# SNAC_USB3-mini.net
KiCad netlist of a schematic drawn in EAGLE
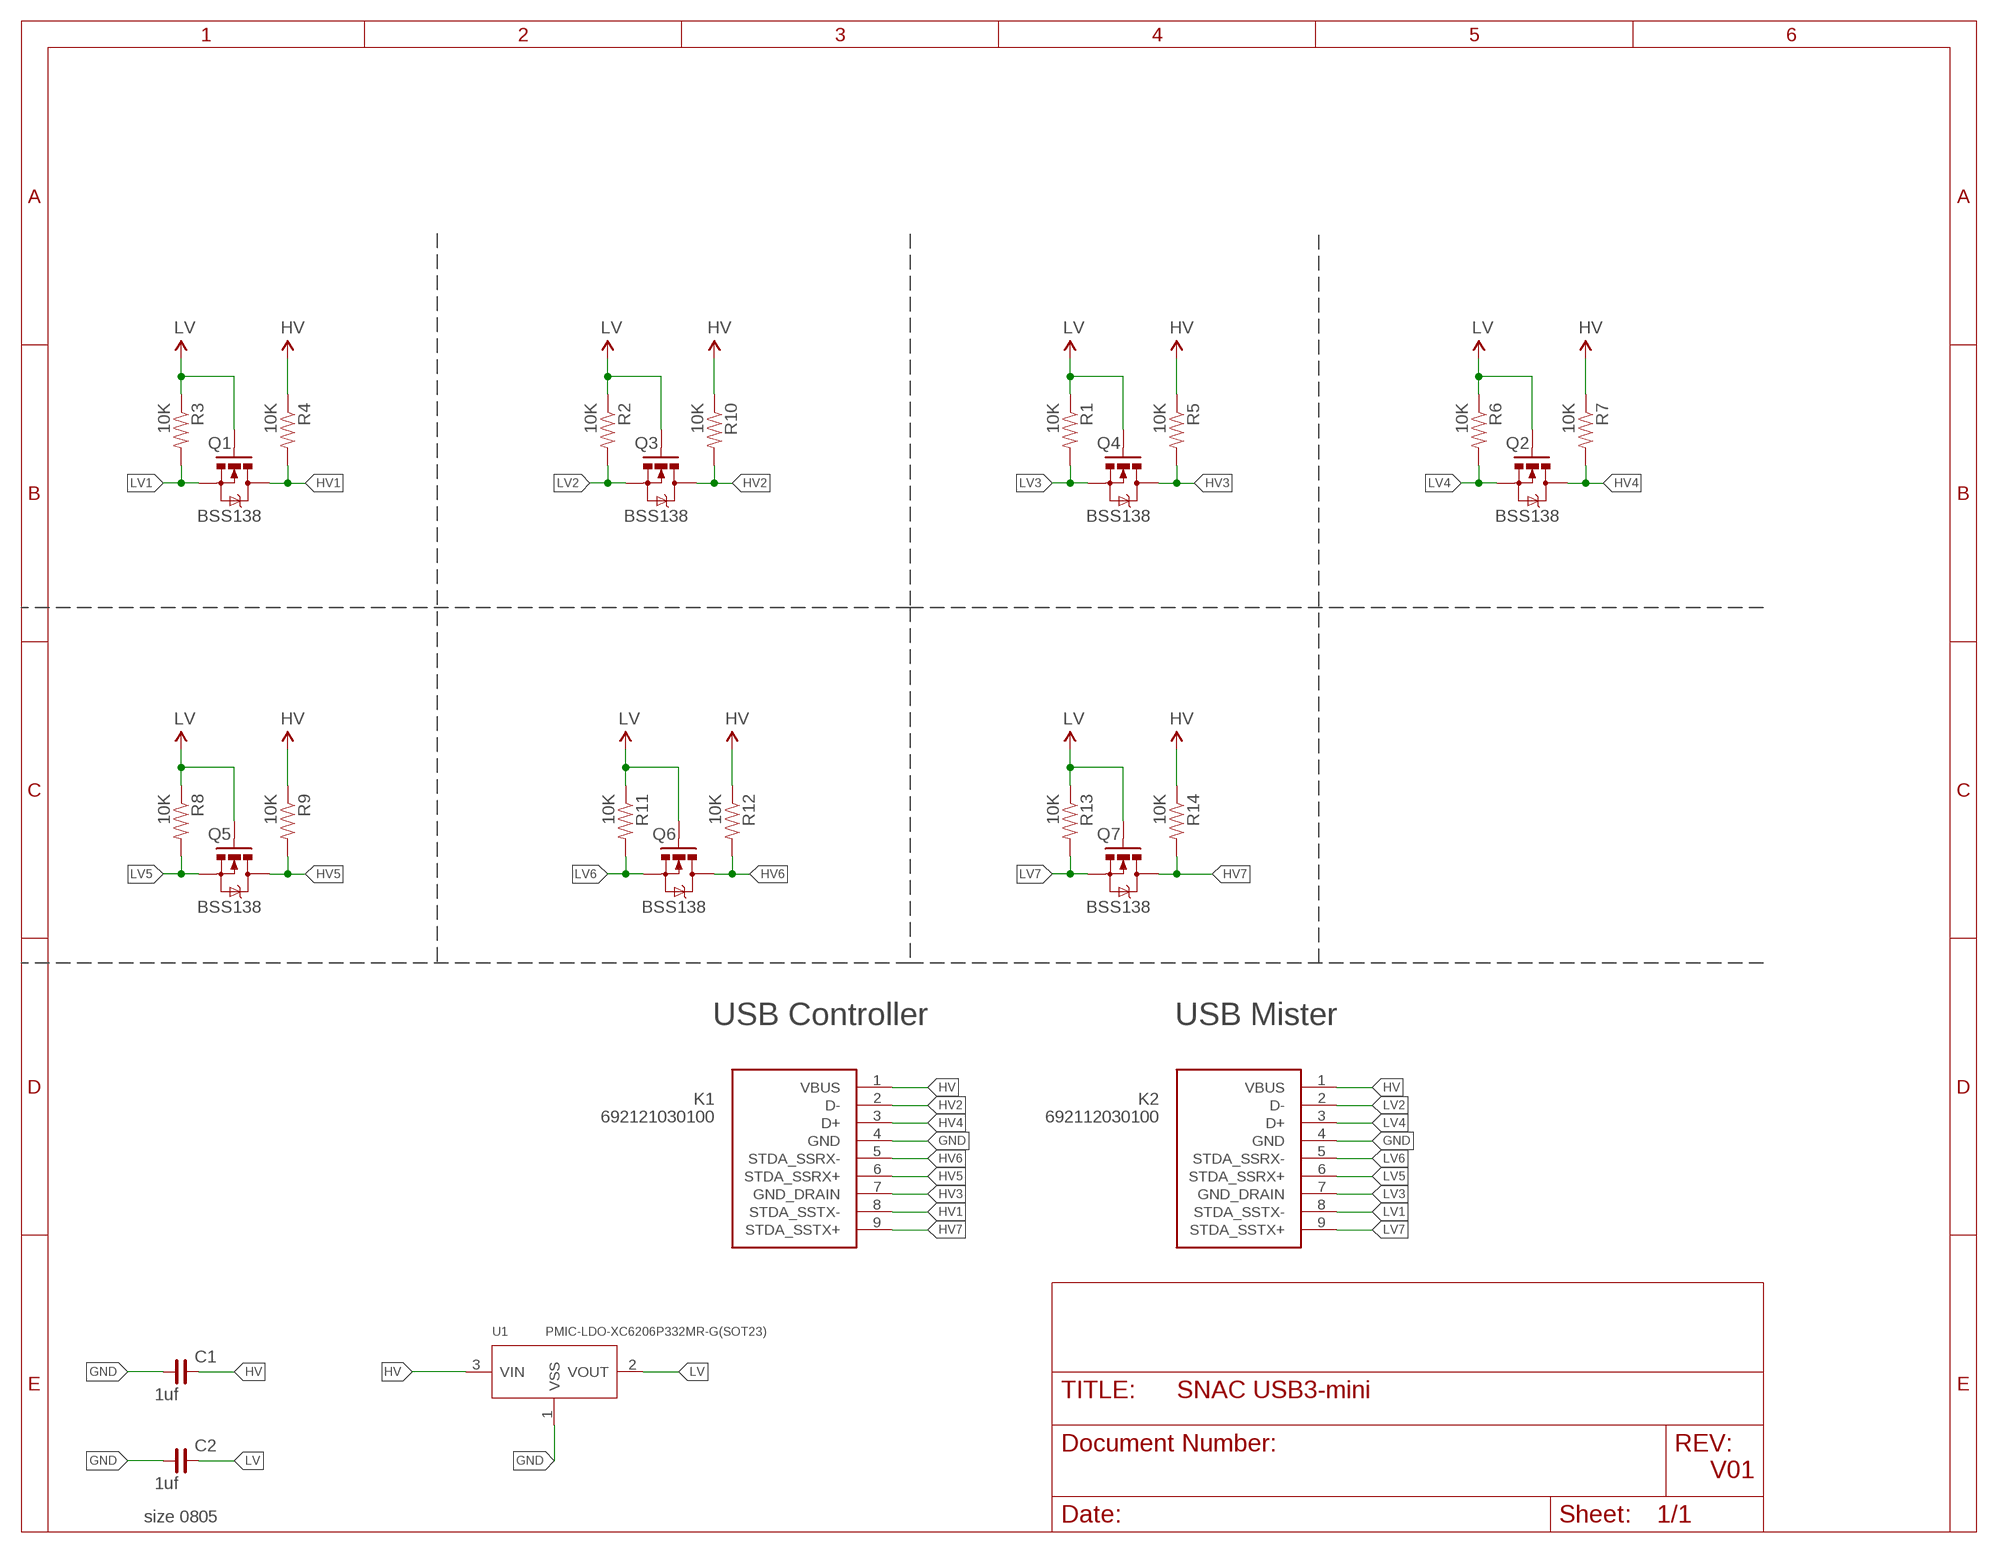
[diagram p0: schematic, sheet 1]

(export (version "E")
  (design (tool "Eeschema 10.0.6"))
  (components
    (comp (ref "C1")
      (value "1uf")
      (footprint "eagle-import:C0805")
      (libsource (lib "eagle-import") (part "C_0805"))
    )
    (comp (ref "C2")
      (value "1uf")
      (footprint "eagle-import:C0805")
      (libsource (lib "eagle-import") (part "C_0805"))
    )
    (comp (ref "K1")
      (value "692121030100")
      (footprint "eagle-import:692121030100")
      (libsource (lib "eagle-import") (part "692121030100"))
    )
    (comp (ref "K2")
      (value "692112030100")
      (footprint "eagle-import:692112030100")
      (libsource (lib "eagle-import") (part "692112030100"))
    )
    (comp (ref "Q1")
      (value "BSS138")
      (footprint "eagle-import:SOT23-3")
      (libsource (lib "eagle-import") (part "MOSFET-NCHANNELSMD"))
    )
    (comp (ref "Q2")
      (value "BSS138")
      (footprint "eagle-import:SOT23-3")
      (libsource (lib "eagle-import") (part "MOSFET-NCHANNELSMD"))
    )
    (comp (ref "Q3")
      (value "BSS138")
      (footprint "eagle-import:SOT23-3")
      (libsource (lib "eagle-import") (part "MOSFET-NCHANNELSMD"))
    )
    (comp (ref "Q4")
      (value "BSS138")
      (footprint "eagle-import:SOT23-3")
      (libsource (lib "eagle-import") (part "MOSFET-NCHANNELSMD"))
    )
    (comp (ref "Q5")
      (value "BSS138")
      (footprint "eagle-import:SOT23-3")
      (libsource (lib "eagle-import") (part "MOSFET-NCHANNELSMD"))
    )
    (comp (ref "Q6")
      (value "BSS138")
      (footprint "eagle-import:SOT23-3")
      (libsource (lib "eagle-import") (part "MOSFET-NCHANNELSMD"))
    )
    (comp (ref "Q7")
      (value "BSS138")
      (footprint "eagle-import:SOT23-3")
      (libsource (lib "eagle-import") (part "MOSFET-NCHANNELSMD"))
    )
    (comp (ref "R1")
      (value "10K")
      (footprint "eagle-import:0603-RES")
      (libsource (lib "eagle-import") (part "RESISTOR0603-RES"))
    )
    (comp (ref "R2")
      (value "10K")
      (footprint "eagle-import:0603-RES")
      (libsource (lib "eagle-import") (part "RESISTOR0603-RES"))
    )
    (comp (ref "R3")
      (value "10K")
      (footprint "eagle-import:0603-RES")
      (libsource (lib "eagle-import") (part "RESISTOR0603-RES"))
    )
    (comp (ref "R4")
      (value "10K")
      (footprint "eagle-import:0603-RES")
      (libsource (lib "eagle-import") (part "RESISTOR0603-RES"))
    )
    (comp (ref "R5")
      (value "10K")
      (footprint "eagle-import:0603-RES")
      (libsource (lib "eagle-import") (part "RESISTOR0603-RES"))
    )
    (comp (ref "R6")
      (value "10K")
      (footprint "eagle-import:0603-RES")
      (libsource (lib "eagle-import") (part "RESISTOR0603-RES"))
    )
    (comp (ref "R7")
      (value "10K")
      (footprint "eagle-import:0603-RES")
      (libsource (lib "eagle-import") (part "RESISTOR0603-RES"))
    )
    (comp (ref "R8")
      (value "10K")
      (footprint "eagle-import:0603-RES")
      (libsource (lib "eagle-import") (part "RESISTOR0603-RES"))
    )
    (comp (ref "R9")
      (value "10K")
      (footprint "eagle-import:0603-RES")
      (libsource (lib "eagle-import") (part "RESISTOR0603-RES"))
    )
    (comp (ref "R10")
      (value "10K")
      (footprint "eagle-import:0603-RES")
      (libsource (lib "eagle-import") (part "RESISTOR0603-RES"))
    )
    (comp (ref "R11")
      (value "10K")
      (footprint "eagle-import:0603-RES")
      (libsource (lib "eagle-import") (part "RESISTOR0603-RES"))
    )
    (comp (ref "R12")
      (value "10K")
      (footprint "eagle-import:0603-RES")
      (libsource (lib "eagle-import") (part "RESISTOR0603-RES"))
    )
    (comp (ref "R13")
      (value "10K")
      (footprint "eagle-import:0603-RES")
      (libsource (lib "eagle-import") (part "RESISTOR0603-RES"))
    )
    (comp (ref "R14")
      (value "10K")
      (footprint "eagle-import:0603-RES")
      (libsource (lib "eagle-import") (part "RESISTOR0603-RES"))
    )
    (comp (ref "U1")
      (value "PMIC-LDO-XC6206P332MR-G(SOT23)")
      (footprint "eagle-import:SOT-23")
      (fields (field (name "MF") "Torex") (field (name "MP") "XC6206P332MR-G"))
      (libsource (lib "eagle-import") (part "PMIC-LDO-XC6206P332MR-G(SOT23)"))
    )
  )
  (nets
    (net (code "1") (name "GND") (class "Default")
      (node (ref "C1") (pin "1") (pinfunction "1_1") (pintype "passive"))
      (node (ref "C2") (pin "1") (pinfunction "1_1") (pintype "passive"))
      (node (ref "K1") (pin "4") (pinfunction "GND_4") (pintype "bidirectional"))
      (node (ref "K2") (pin "4") (pinfunction "GND_4") (pintype "bidirectional"))
      (node (ref "U1") (pin "1") (pinfunction "VSS_1") (pintype "power_in"))
    )
    (net (code "2") (name "HV") (class "Default")
      (node (ref "C1") (pin "2") (pinfunction "2_2") (pintype "passive"))
      (node (ref "K1") (pin "1") (pinfunction "VBUS_1") (pintype "bidirectional"))
      (node (ref "K2") (pin "1") (pinfunction "VBUS_1") (pintype "bidirectional"))
      (node (ref "R10") (pin "1") (pinfunction "1_1") (pintype "passive"))
      (node (ref "R12") (pin "1") (pinfunction "1_1") (pintype "passive"))
      (node (ref "R14") (pin "1") (pinfunction "1_1") (pintype "passive"))
      (node (ref "R4") (pin "1") (pinfunction "1_1") (pintype "passive"))
      (node (ref "R5") (pin "1") (pinfunction "1_1") (pintype "passive"))
      (node (ref "R7") (pin "1") (pinfunction "1_1") (pintype "passive"))
      (node (ref "R9") (pin "1") (pinfunction "1_1") (pintype "passive"))
      (node (ref "U1") (pin "3") (pinfunction "VIN_3") (pintype "input"))
    )
    (net (code "3") (name "HV1") (class "Default")
      (node (ref "K1") (pin "8") (pinfunction "STDA_SSTX-_8") (pintype "bidirectional"))
      (node (ref "Q1") (pin "3") (pinfunction "D_3") (pintype "passive"))
      (node (ref "R4") (pin "2") (pinfunction "2_2") (pintype "passive"))
    )
    (net (code "4") (name "HV2") (class "Default")
      (node (ref "K1") (pin "2") (pinfunction "D-_2") (pintype "bidirectional"))
      (node (ref "Q3") (pin "3") (pinfunction "D_3") (pintype "passive"))
      (node (ref "R10") (pin "2") (pinfunction "2_2") (pintype "passive"))
    )
    (net (code "5") (name "HV3") (class "Default")
      (node (ref "K1") (pin "7") (pinfunction "GND_DRAIN_7") (pintype "bidirectional"))
      (node (ref "Q4") (pin "3") (pinfunction "D_3") (pintype "passive"))
      (node (ref "R5") (pin "2") (pinfunction "2_2") (pintype "passive"))
    )
    (net (code "6") (name "HV4") (class "Default")
      (node (ref "K1") (pin "3") (pinfunction "D+_3") (pintype "bidirectional"))
      (node (ref "Q2") (pin "3") (pinfunction "D_3") (pintype "passive"))
      (node (ref "R7") (pin "2") (pinfunction "2_2") (pintype "passive"))
    )
    (net (code "7") (name "HV5") (class "Default")
      (node (ref "K1") (pin "6") (pinfunction "STDA_SSRX+_6") (pintype "bidirectional"))
      (node (ref "Q5") (pin "3") (pinfunction "D_3") (pintype "passive"))
      (node (ref "R9") (pin "2") (pinfunction "2_2") (pintype "passive"))
    )
    (net (code "8") (name "HV6") (class "Default")
      (node (ref "K1") (pin "5") (pinfunction "STDA_SSRX-_5") (pintype "bidirectional"))
      (node (ref "Q6") (pin "3") (pinfunction "D_3") (pintype "passive"))
      (node (ref "R12") (pin "2") (pinfunction "2_2") (pintype "passive"))
    )
    (net (code "9") (name "HV7") (class "Default")
      (node (ref "K1") (pin "9") (pinfunction "STDA_SSTX+_9") (pintype "bidirectional"))
      (node (ref "Q7") (pin "3") (pinfunction "D_3") (pintype "passive"))
      (node (ref "R14") (pin "2") (pinfunction "2_2") (pintype "passive"))
    )
    (net (code "10") (name "LV") (class "Default")
      (node (ref "C2") (pin "2") (pinfunction "2_2") (pintype "passive"))
      (node (ref "Q1") (pin "1") (pinfunction "G_1") (pintype "passive"))
      (node (ref "Q2") (pin "1") (pinfunction "G_1") (pintype "passive"))
      (node (ref "Q3") (pin "1") (pinfunction "G_1") (pintype "passive"))
      (node (ref "Q4") (pin "1") (pinfunction "G_1") (pintype "passive"))
      (node (ref "Q5") (pin "1") (pinfunction "G_1") (pintype "passive"))
      (node (ref "Q6") (pin "1") (pinfunction "G_1") (pintype "passive"))
      (node (ref "Q7") (pin "1") (pinfunction "G_1") (pintype "passive"))
      (node (ref "R1") (pin "1") (pinfunction "1_1") (pintype "passive"))
      (node (ref "R11") (pin "1") (pinfunction "1_1") (pintype "passive"))
      (node (ref "R13") (pin "1") (pinfunction "1_1") (pintype "passive"))
      (node (ref "R2") (pin "1") (pinfunction "1_1") (pintype "passive"))
      (node (ref "R3") (pin "1") (pinfunction "1_1") (pintype "passive"))
      (node (ref "R6") (pin "1") (pinfunction "1_1") (pintype "passive"))
      (node (ref "R8") (pin "1") (pinfunction "1_1") (pintype "passive"))
      (node (ref "U1") (pin "2") (pinfunction "VOUT_2") (pintype "output"))
    )
    (net (code "11") (name "LV1") (class "Default")
      (node (ref "K2") (pin "8") (pinfunction "STDA_SSTX-_8") (pintype "bidirectional"))
      (node (ref "Q1") (pin "2") (pinfunction "S_2") (pintype "passive"))
      (node (ref "R3") (pin "2") (pinfunction "2_2") (pintype "passive"))
    )
    (net (code "12") (name "LV2") (class "Default")
      (node (ref "K2") (pin "2") (pinfunction "D-_2") (pintype "bidirectional"))
      (node (ref "Q3") (pin "2") (pinfunction "S_2") (pintype "passive"))
      (node (ref "R2") (pin "2") (pinfunction "2_2") (pintype "passive"))
    )
    (net (code "13") (name "LV3") (class "Default")
      (node (ref "K2") (pin "7") (pinfunction "GND_DRAIN_7") (pintype "bidirectional"))
      (node (ref "Q4") (pin "2") (pinfunction "S_2") (pintype "passive"))
      (node (ref "R1") (pin "2") (pinfunction "2_2") (pintype "passive"))
    )
    (net (code "14") (name "LV4") (class "Default")
      (node (ref "K2") (pin "3") (pinfunction "D+_3") (pintype "bidirectional"))
      (node (ref "Q2") (pin "2") (pinfunction "S_2") (pintype "passive"))
      (node (ref "R6") (pin "2") (pinfunction "2_2") (pintype "passive"))
    )
    (net (code "15") (name "LV5") (class "Default")
      (node (ref "K2") (pin "6") (pinfunction "STDA_SSRX+_6") (pintype "bidirectional"))
      (node (ref "Q5") (pin "2") (pinfunction "S_2") (pintype "passive"))
      (node (ref "R8") (pin "2") (pinfunction "2_2") (pintype "passive"))
    )
    (net (code "16") (name "LV6") (class "Default")
      (node (ref "K2") (pin "5") (pinfunction "STDA_SSRX-_5") (pintype "bidirectional"))
      (node (ref "Q6") (pin "2") (pinfunction "S_2") (pintype "passive"))
      (node (ref "R11") (pin "2") (pinfunction "2_2") (pintype "passive"))
    )
    (net (code "17") (name "LV7") (class "Default")
      (node (ref "K2") (pin "9") (pinfunction "STDA_SSTX+_9") (pintype "bidirectional"))
      (node (ref "Q7") (pin "2") (pinfunction "S_2") (pintype "passive"))
      (node (ref "R13") (pin "2") (pinfunction "2_2") (pintype "passive"))
    )
  )
)
